# obc-v2_CM4-CSI.net
KiCad netlist of a schematic drawn in Altium Designer
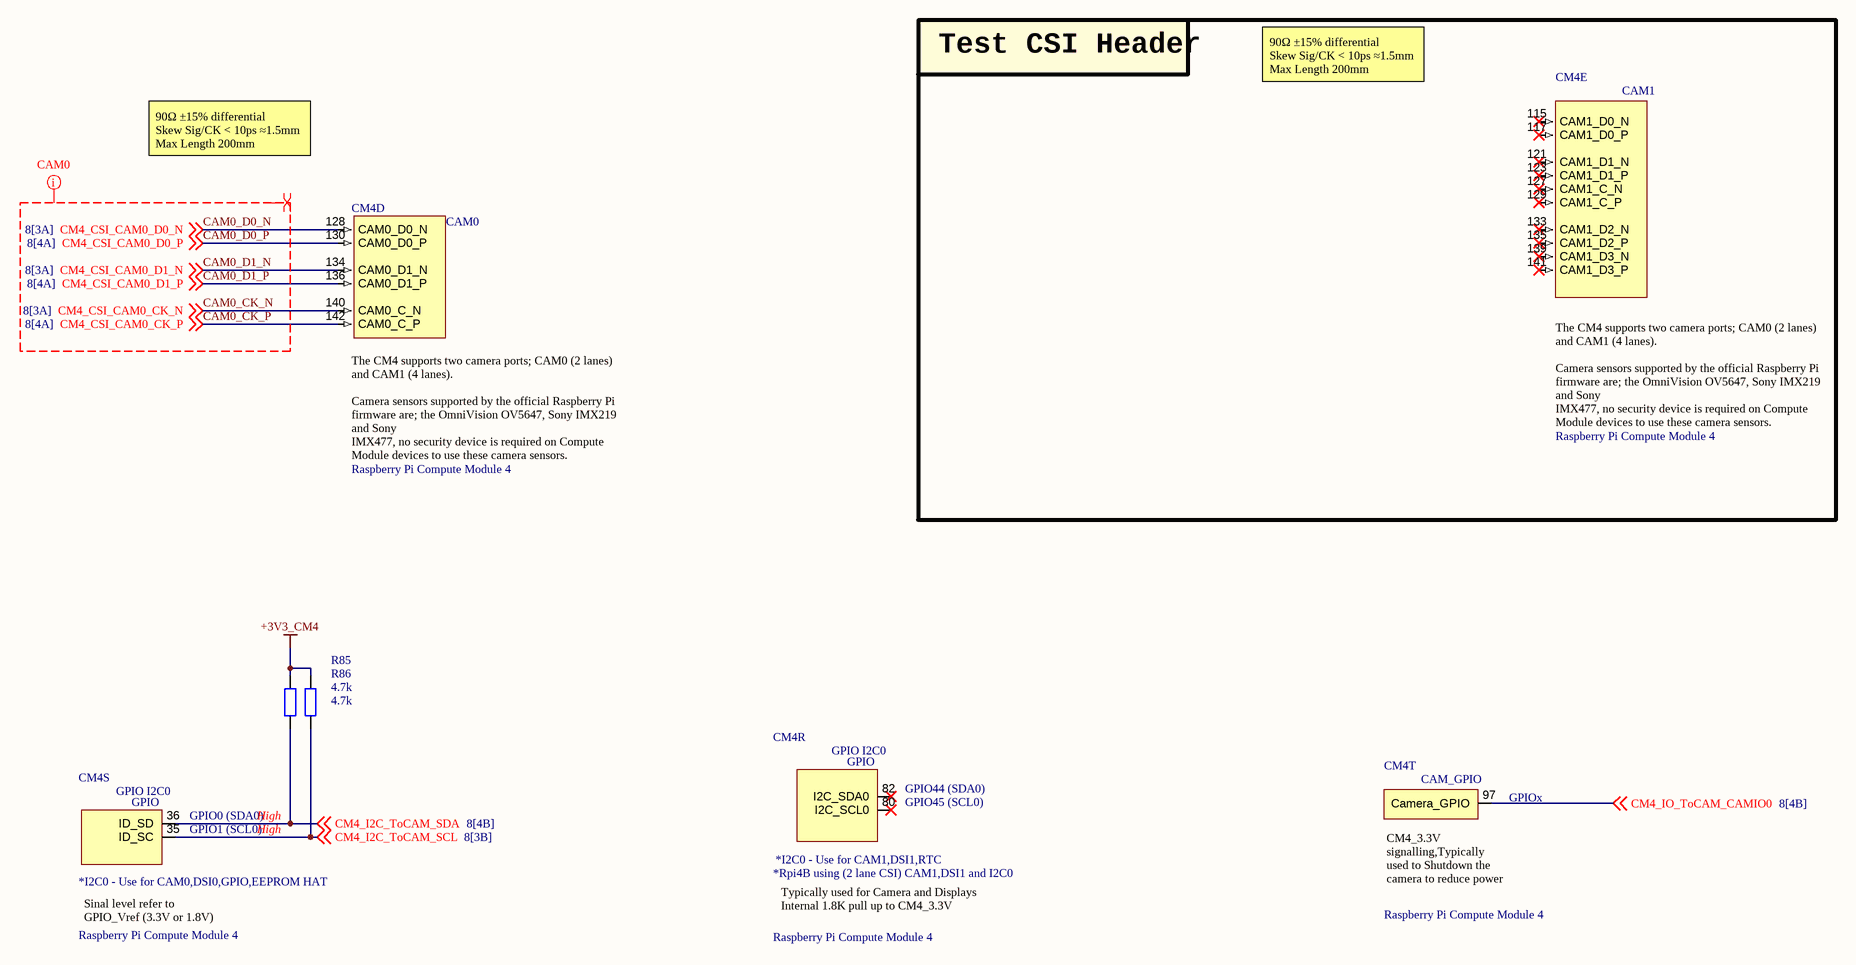
[diagram p0: obc-v2_CM4-CSI.SchDoc]

(export (version "E")
  (design (tool "Eeschema 10.0.6"))
  (components
    (comp (ref "CM4")
      (value "Raspberry Pi Compute Module 4")
      (footprint "CM4-DF40HC(3.0)-100DS-0.4v_3mm_1.5mm")
      (description "Raspberry Pi Compute Module 4 by Amornthep Phunsin")
      (libsource (lib "CM4") (part "CM4"))
    )
    (comp (ref "R85")
      (value "4.7k")
      (footprint "RES_C_1608X60")
      (description "RES")
      (libsource (lib "Altium_Lib_by_KhueNguyenCreator") (part "Tro 0603 1% 10k"))
    )
    (comp (ref "R86")
      (value "4.7k")
      (footprint "RES_C_1608X60")
      (description "RES")
      (libsource (lib "Altium_Lib_by_KhueNguyenCreator") (part "Tro 0603 1% 10k"))
    )
  )
  (nets
    (net (code "1") (name "+3V3_CM4") (class "Default")
      (node (ref "R85") (pin "1") (pinfunction "1_1") (pintype "passive"))
      (node (ref "R86") (pin "1") (pinfunction "1_1") (pintype "passive"))
    )
    (net (code "2") (name "CM4_CSI_CAM0_CK_N") (class "Default")
      (node (ref "CM4") (pin "140") (pinfunction "CAM0_C_N_140") (pintype "input"))
    )
    (net (code "3") (name "CM4_CSI_CAM0_CK_P") (class "Default")
      (node (ref "CM4") (pin "142") (pinfunction "CAM0_C_P_142") (pintype "input"))
    )
    (net (code "4") (name "CM4_CSI_CAM0_D0_N") (class "Default")
      (node (ref "CM4") (pin "128") (pinfunction "CAM0_D0_N_128") (pintype "input"))
    )
    (net (code "5") (name "CM4_CSI_CAM0_D0_P") (class "Default")
      (node (ref "CM4") (pin "130") (pinfunction "CAM0_D0_P_130") (pintype "input"))
    )
    (net (code "6") (name "CM4_CSI_CAM0_D1_N") (class "Default")
      (node (ref "CM4") (pin "134") (pinfunction "CAM0_D1_N_134") (pintype "input"))
    )
    (net (code "7") (name "CM4_CSI_CAM0_D1_P") (class "Default")
      (node (ref "CM4") (pin "136") (pinfunction "CAM0_D1_P_136") (pintype "input"))
    )
    (net (code "8") (name "CM4_I2C_ToCAM_SCL") (class "Default")
      (node (ref "CM4") (pin "35") (pinfunction "ID_SC_35") (pintype "passive"))
      (node (ref "R86") (pin "2") (pinfunction "2_2") (pintype "passive"))
    )
    (net (code "9") (name "CM4_I2C_ToCAM_SDA") (class "Default")
      (node (ref "CM4") (pin "36") (pinfunction "ID_SD_36") (pintype "passive"))
      (node (ref "R85") (pin "2") (pinfunction "2_2") (pintype "passive"))
    )
    (net (code "10") (name "CM4_IO_ToCAM_CAMIO0") (class "Default")
      (node (ref "CM4") (pin "97") (pinfunction "Camera_GPIO_97") (pintype "passive"))
    )
    (net (code "11") (name "unconnected-(CM4E-CAM1_C_N-Pad127)") (class "Default")
      (node (ref "CM4") (pin "127") (pinfunction "CAM1_C_N_127") (pintype "input+no_connect"))
    )
    (net (code "12") (name "unconnected-(CM4E-CAM1_C_P-Pad129)") (class "Default")
      (node (ref "CM4") (pin "129") (pinfunction "CAM1_C_P_129") (pintype "input+no_connect"))
    )
    (net (code "13") (name "unconnected-(CM4E-CAM1_D0_N-Pad115)") (class "Default")
      (node (ref "CM4") (pin "115") (pinfunction "CAM1_D0_N_115") (pintype "input+no_connect"))
    )
    (net (code "14") (name "unconnected-(CM4E-CAM1_D0_P-Pad117)") (class "Default")
      (node (ref "CM4") (pin "117") (pinfunction "CAM1_D0_P_117") (pintype "input+no_connect"))
    )
    (net (code "15") (name "unconnected-(CM4E-CAM1_D1_N-Pad121)") (class "Default")
      (node (ref "CM4") (pin "121") (pinfunction "CAM1_D1_N_121") (pintype "input+no_connect"))
    )
    (net (code "16") (name "unconnected-(CM4E-CAM1_D1_P-Pad123)") (class "Default")
      (node (ref "CM4") (pin "123") (pinfunction "CAM1_D1_P_123") (pintype "input+no_connect"))
    )
    (net (code "17") (name "unconnected-(CM4E-CAM1_D2_N-Pad133)") (class "Default")
      (node (ref "CM4") (pin "133") (pinfunction "CAM1_D2_N_133") (pintype "input+no_connect"))
    )
    (net (code "18") (name "unconnected-(CM4E-CAM1_D2_P-Pad135)") (class "Default")
      (node (ref "CM4") (pin "135") (pinfunction "CAM1_D2_P_135") (pintype "input+no_connect"))
    )
    (net (code "19") (name "unconnected-(CM4E-CAM1_D3_N-Pad139)") (class "Default")
      (node (ref "CM4") (pin "139") (pinfunction "CAM1_D3_N_139") (pintype "input+no_connect"))
    )
    (net (code "20") (name "unconnected-(CM4E-CAM1_D3_P-Pad141)") (class "Default")
      (node (ref "CM4") (pin "141") (pinfunction "CAM1_D3_P_141") (pintype "input+no_connect"))
    )
    (net (code "21") (name "unconnected-(CM4R-I2C_SCL0-Pad80)") (class "Default")
      (node (ref "CM4") (pin "80") (pinfunction "I2C_SCL0_80") (pintype "passive+no_connect"))
    )
    (net (code "22") (name "unconnected-(CM4R-I2C_SDA0-Pad82)") (class "Default")
      (node (ref "CM4") (pin "82") (pinfunction "I2C_SDA0_82") (pintype "passive+no_connect"))
    )
  )
)
